# Slave4_flying_pcb_v1.net
KiCad netlist of a schematic drawn in Altium Designer
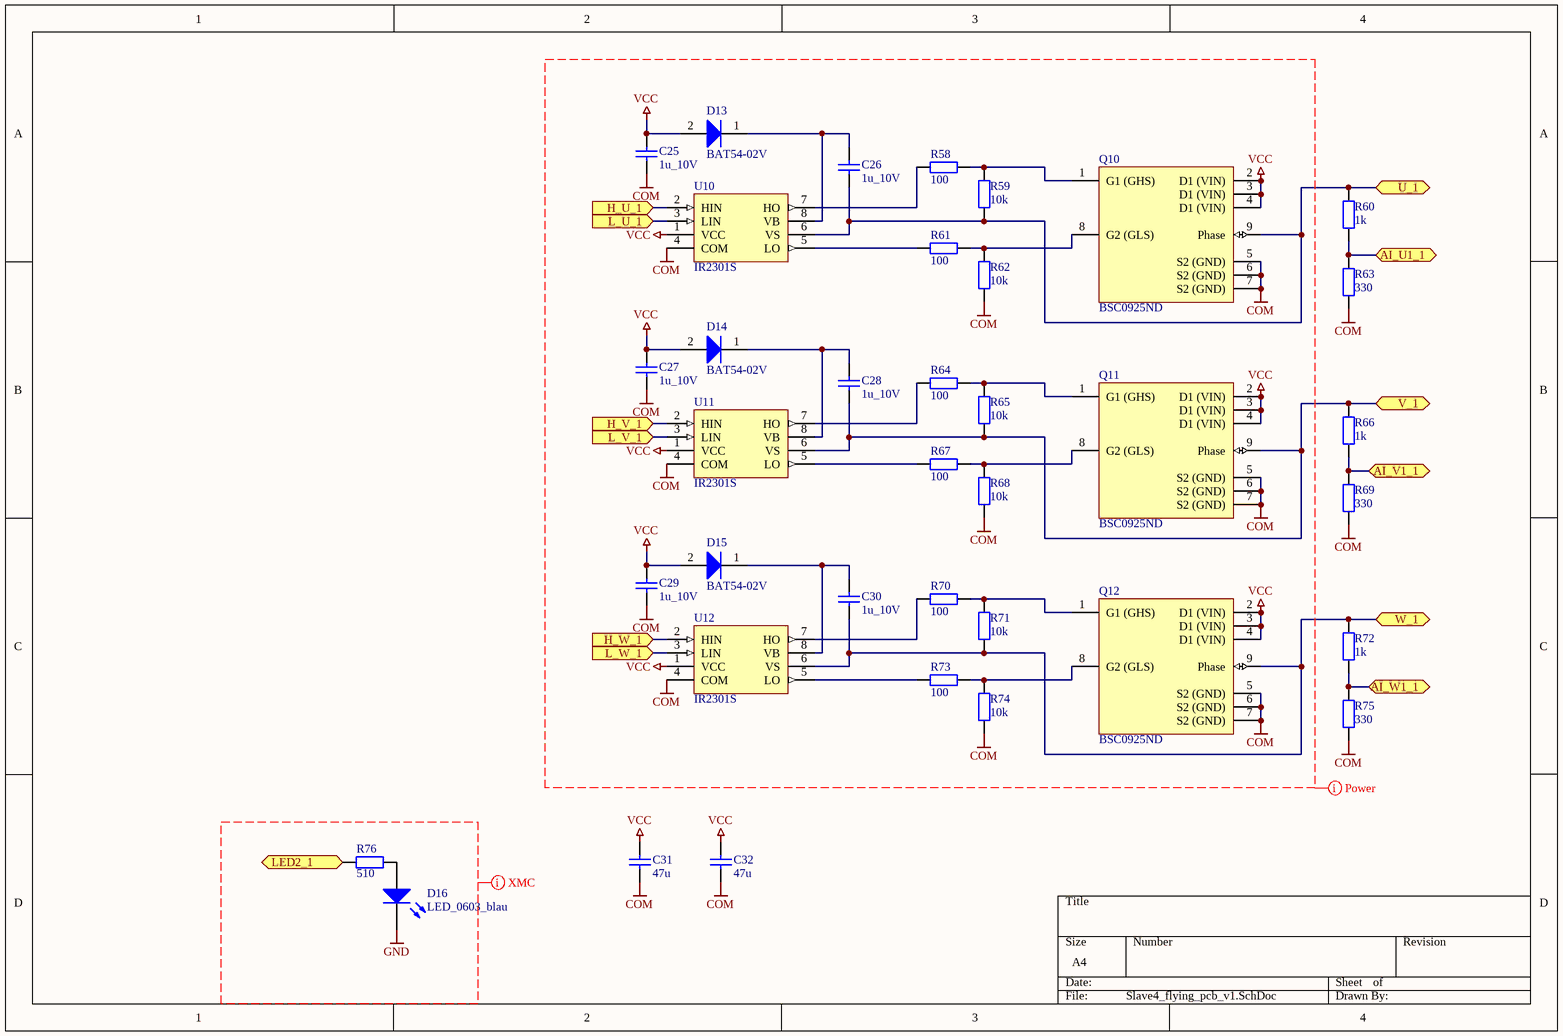
[diagram p0: Slave4_flying_pcb_v1.SchDoc]

(export (version "E")
  (design (tool "Eeschema 10.0.6"))
  (components
    (comp (ref "C25")
      (value "1u_10V")
      (footprint "1608[0603]")
      (fields (field (name "VOLTAGE") "10V"))
      (libsource (lib "Capacitors$") (part "Cap_133"))
    )
    (comp (ref "C26")
      (value "1u_10V")
      (footprint "1608[0603]")
      (fields (field (name "VOLTAGE") "10V"))
      (libsource (lib "Capacitors$") (part "Cap_133"))
    )
    (comp (ref "C27")
      (value "1u_10V")
      (footprint "1608[0603]")
      (fields (field (name "VOLTAGE") "10V"))
      (libsource (lib "Capacitors$") (part "Cap_133"))
    )
    (comp (ref "C28")
      (value "1u_10V")
      (footprint "1608[0603]")
      (fields (field (name "VOLTAGE") "10V"))
      (libsource (lib "Capacitors$") (part "Cap_133"))
    )
    (comp (ref "C29")
      (value "1u_10V")
      (footprint "1608[0603]")
      (fields (field (name "VOLTAGE") "10V"))
      (libsource (lib "Capacitors$") (part "Cap_133"))
    )
    (comp (ref "C30")
      (value "1u_10V")
      (footprint "1608[0603]")
      (fields (field (name "VOLTAGE") "10V"))
      (libsource (lib "Capacitors$") (part "Cap_133"))
    )
    (comp (ref "C31")
      (value "47u")
      (footprint "_0805")
      (fields (field (name "VOLTAGE") "50V"))
      (libsource (lib "Capacitors$") (part "Cap_133"))
    )
    (comp (ref "C32")
      (value "47u")
      (footprint "_0805")
      (fields (field (name "VOLTAGE") "50V"))
      (libsource (lib "Capacitors$") (part "Cap_133"))
    )
    (comp (ref "D13")
      (value "BAT54-02V")
      (footprint "INF-SC79_V")
      (description "Silicon Schottky Diode, SC79, Reel, Green")
      (fields (field (name "MANUFACTURER") "Infineon"))
      (libsource (lib "Pinus_V2") (part "BAT54-02V"))
    )
    (comp (ref "D14")
      (value "BAT54-02V")
      (footprint "INF-SC79_V")
      (description "Silicon Schottky Diode, SC79, Reel, Green")
      (fields (field (name "MANUFACTURER") "Infineon"))
      (libsource (lib "Pinus_V2") (part "BAT54-02V"))
    )
    (comp (ref "D15")
      (value "BAT54-02V")
      (footprint "INF-SC79_V")
      (description "Silicon Schottky Diode, SC79, Reel, Green")
      (fields (field (name "MANUFACTURER") "Infineon"))
      (libsource (lib "Pinus_V2") (part "BAT54-02V"))
    )
    (comp (ref "D16")
      (value "LED_0603_blau")
      (footprint "LED_0603")
      (libsource (lib "flying_pcb_v1") (part "DIODE_60"))
    )
    (comp (ref "Q10")
      (value "BSC0925ND")
      (footprint "INF-PG-TISON-8_V")
      (description "N-Channel OptiMOS Power-MOSFET, 30 V VDS, 40 A ID, -55 to 150 degC, PG-TISON-8, Reel, Green")
      (fields (field (name "MANUFACTURER") "Infineon"))
      (libsource (lib "Pinus_V2") (part "BSC0925ND"))
    )
    (comp (ref "Q11")
      (value "BSC0925ND")
      (footprint "INF-PG-TISON-8_V")
      (description "N-Channel OptiMOS Power-MOSFET, 30 V VDS, 40 A ID, -55 to 150 degC, PG-TISON-8, Reel, Green")
      (fields (field (name "MANUFACTURER") "Infineon"))
      (libsource (lib "Pinus_V2") (part "BSC0925ND"))
    )
    (comp (ref "Q12")
      (value "BSC0925ND")
      (footprint "INF-PG-TISON-8_V")
      (description "N-Channel OptiMOS Power-MOSFET, 30 V VDS, 40 A ID, -55 to 150 degC, PG-TISON-8, Reel, Green")
      (fields (field (name "MANUFACTURER") "Infineon"))
      (libsource (lib "Pinus_V2") (part "BSC0925ND"))
    )
    (comp (ref "R58")
      (value "100")
      (footprint "1608[0603]")
      (fields (field (name "Comment") "Res_0603"))
      (libsource (lib "") (part "Res_6_1"))
    )
    (comp (ref "R59")
      (value "10k")
      (footprint "1608[0603]")
      (fields (field (name "Comment") "Res_0603"))
      (libsource (lib "Resistors$") (part "Res_6"))
    )
    (comp (ref "R60")
      (value "1k")
      (footprint "1608[0603]")
      (fields (field (name "Comment") "Res_0603"))
      (libsource (lib "Resistors$") (part "Res_6"))
    )
    (comp (ref "R61")
      (value "100")
      (footprint "1608[0603]")
      (fields (field (name "Comment") "Res_0603"))
      (libsource (lib "") (part "Res_6_1"))
    )
    (comp (ref "R62")
      (value "10k")
      (footprint "1608[0603]")
      (fields (field (name "Comment") "Res_0603"))
      (libsource (lib "Resistors$") (part "Res_6"))
    )
    (comp (ref "R63")
      (value "330")
      (footprint "1608[0603]")
      (fields (field (name "Comment") "Res_0603"))
      (libsource (lib "Resistors$") (part "Res_6"))
    )
    (comp (ref "R64")
      (value "100")
      (footprint "1608[0603]")
      (fields (field (name "Comment") "Res_0603"))
      (libsource (lib "") (part "Res_6_1"))
    )
    (comp (ref "R65")
      (value "10k")
      (footprint "1608[0603]")
      (fields (field (name "Comment") "Res_0603"))
      (libsource (lib "Resistors$") (part "Res_6"))
    )
    (comp (ref "R66")
      (value "1k")
      (footprint "1608[0603]")
      (fields (field (name "Comment") "Res_0603"))
      (libsource (lib "Resistors$") (part "Res_6"))
    )
    (comp (ref "R67")
      (value "100")
      (footprint "1608[0603]")
      (fields (field (name "Comment") "Res_0603"))
      (libsource (lib "") (part "Res_6_1"))
    )
    (comp (ref "R68")
      (value "10k")
      (footprint "1608[0603]")
      (fields (field (name "Comment") "Res_0603"))
      (libsource (lib "Resistors$") (part "Res_6"))
    )
    (comp (ref "R69")
      (value "330")
      (footprint "1608[0603]")
      (fields (field (name "Comment") "Res_0603"))
      (libsource (lib "Resistors$") (part "Res_6"))
    )
    (comp (ref "R70")
      (value "100")
      (footprint "1608[0603]")
      (fields (field (name "Comment") "Res_0603"))
      (libsource (lib "") (part "Res_6_1"))
    )
    (comp (ref "R71")
      (value "10k")
      (footprint "1608[0603]")
      (fields (field (name "Comment") "Res_0603"))
      (libsource (lib "Resistors$") (part "Res_6"))
    )
    (comp (ref "R72")
      (value "1k")
      (footprint "1608[0603]")
      (fields (field (name "Comment") "Res_0603"))
      (libsource (lib "Resistors$") (part "Res_6"))
    )
    (comp (ref "R73")
      (value "100")
      (footprint "1608[0603]")
      (fields (field (name "Comment") "Res_0603"))
      (libsource (lib "") (part "Res_6_1"))
    )
    (comp (ref "R74")
      (value "10k")
      (footprint "1608[0603]")
      (fields (field (name "Comment") "Res_0603"))
      (libsource (lib "Resistors$") (part "Res_6"))
    )
    (comp (ref "R75")
      (value "330")
      (footprint "1608[0603]")
      (fields (field (name "Comment") "Res_0603"))
      (libsource (lib "Resistors$") (part "Res_6"))
    )
    (comp (ref "R76")
      (value "510")
      (footprint "1608[0603]")
      (fields (field (name "Comment") "Res_0603"))
      (libsource (lib "") (part "Res_6_2"))
    )
    (comp (ref "U10")
      (value "IR2301S")
      (footprint "SO-8_N")
      (description "High and Low Side Driver")
      (fields (field (name "PUBLISHER") "Altium Limited"))
      (libsource (lib "Pinus_V2") (part "IR2101S"))
    )
    (comp (ref "U11")
      (value "IR2301S")
      (footprint "SO-8_N")
      (description "High and Low Side Driver")
      (fields (field (name "PUBLISHER") "Altium Limited"))
      (libsource (lib "Pinus_V2") (part "IR2101S"))
    )
    (comp (ref "U12")
      (value "IR2301S")
      (footprint "SO-8_N")
      (description "High and Low Side Driver")
      (fields (field (name "PUBLISHER") "Altium Limited"))
      (libsource (lib "Pinus_V2") (part "IR2101S"))
    )
  )
  (nets
    (net (code "1") (name "/AI_U1_1") (class "Default")
      (node (ref "R60") (pin "2") (pinfunction "2_2") (pintype "passive"))
      (node (ref "R63") (pin "1") (pinfunction "1_1") (pintype "passive"))
    )
    (net (code "2") (name "/AI_V1_1") (class "Default")
      (node (ref "R66") (pin "2") (pinfunction "2_2") (pintype "passive"))
      (node (ref "R69") (pin "1") (pinfunction "1_1") (pintype "passive"))
    )
    (net (code "3") (name "/AI_W1_1") (class "Default")
      (node (ref "R72") (pin "2") (pinfunction "2_2") (pintype "passive"))
      (node (ref "R75") (pin "1") (pinfunction "1_1") (pintype "passive"))
    )
    (net (code "4") (name "/H_U_1") (class "Default")
      (node (ref "U10") (pin "2") (pinfunction "HIN_2") (pintype "input"))
    )
    (net (code "5") (name "/H_V_1") (class "Default")
      (node (ref "U11") (pin "2") (pinfunction "HIN_2") (pintype "input"))
    )
    (net (code "6") (name "/H_W_1") (class "Default")
      (node (ref "U12") (pin "2") (pinfunction "HIN_2") (pintype "input"))
    )
    (net (code "7") (name "/LED2_1") (class "Default")
      (node (ref "R76") (pin "1") (pinfunction "1_1") (pintype "passive"))
    )
    (net (code "8") (name "/L_U_1") (class "Default")
      (node (ref "U10") (pin "3") (pinfunction "LIN_3") (pintype "input"))
    )
    (net (code "9") (name "/L_V_1") (class "Default")
      (node (ref "U11") (pin "3") (pinfunction "LIN_3") (pintype "input"))
    )
    (net (code "10") (name "/L_W_1") (class "Default")
      (node (ref "U12") (pin "3") (pinfunction "LIN_3") (pintype "input"))
    )
    (net (code "11") (name "/U_1") (class "Default")
      (node (ref "C26") (pin "2") (pinfunction "2_2") (pintype "passive"))
      (node (ref "Q10") (pin "9") (pinfunction "Phase_9") (pintype "bidirectional"))
      (node (ref "R59") (pin "2") (pinfunction "2_2") (pintype "passive"))
      (node (ref "R60") (pin "1") (pinfunction "1_1") (pintype "passive"))
      (node (ref "U10") (pin "6") (pinfunction "VS_6") (pintype "power_in"))
    )
    (net (code "12") (name "/V_1") (class "Default")
      (node (ref "C28") (pin "2") (pinfunction "2_2") (pintype "passive"))
      (node (ref "Q11") (pin "9") (pinfunction "Phase_9") (pintype "bidirectional"))
      (node (ref "R65") (pin "2") (pinfunction "2_2") (pintype "passive"))
      (node (ref "R66") (pin "1") (pinfunction "1_1") (pintype "passive"))
      (node (ref "U11") (pin "6") (pinfunction "VS_6") (pintype "power_in"))
    )
    (net (code "13") (name "/W_1") (class "Default")
      (node (ref "C30") (pin "2") (pinfunction "2_2") (pintype "passive"))
      (node (ref "Q12") (pin "9") (pinfunction "Phase_9") (pintype "bidirectional"))
      (node (ref "R71") (pin "2") (pinfunction "2_2") (pintype "passive"))
      (node (ref "R72") (pin "1") (pinfunction "1_1") (pintype "passive"))
      (node (ref "U12") (pin "6") (pinfunction "VS_6") (pintype "power_in"))
    )
    (net (code "14") (name "COM") (class "Default")
      (node (ref "C25") (pin "2") (pinfunction "2_2") (pintype "passive"))
      (node (ref "C27") (pin "2") (pinfunction "2_2") (pintype "passive"))
      (node (ref "C29") (pin "2") (pinfunction "2_2") (pintype "passive"))
      (node (ref "C31") (pin "1") (pinfunction "1_1") (pintype "passive"))
      (node (ref "C32") (pin "1") (pinfunction "1_1") (pintype "passive"))
      (node (ref "Q10") (pin "5") (pinfunction "S2_(GND)_5") (pintype "passive"))
      (node (ref "Q10") (pin "6") (pinfunction "S2_(GND)_6") (pintype "passive"))
      (node (ref "Q10") (pin "7") (pinfunction "S2_(GND)_7") (pintype "passive"))
      (node (ref "Q11") (pin "5") (pinfunction "S2_(GND)_5") (pintype "passive"))
      (node (ref "Q11") (pin "6") (pinfunction "S2_(GND)_6") (pintype "passive"))
      (node (ref "Q11") (pin "7") (pinfunction "S2_(GND)_7") (pintype "passive"))
      (node (ref "Q12") (pin "5") (pinfunction "S2_(GND)_5") (pintype "passive"))
      (node (ref "Q12") (pin "6") (pinfunction "S2_(GND)_6") (pintype "passive"))
      (node (ref "Q12") (pin "7") (pinfunction "S2_(GND)_7") (pintype "passive"))
      (node (ref "R62") (pin "2") (pinfunction "2_2") (pintype "passive"))
      (node (ref "R63") (pin "2") (pinfunction "2_2") (pintype "passive"))
      (node (ref "R68") (pin "2") (pinfunction "2_2") (pintype "passive"))
      (node (ref "R69") (pin "2") (pinfunction "2_2") (pintype "passive"))
      (node (ref "R74") (pin "2") (pinfunction "2_2") (pintype "passive"))
      (node (ref "R75") (pin "2") (pinfunction "2_2") (pintype "passive"))
      (node (ref "U10") (pin "4") (pinfunction "COM_4") (pintype "power_in"))
      (node (ref "U11") (pin "4") (pinfunction "COM_4") (pintype "power_in"))
      (node (ref "U12") (pin "4") (pinfunction "COM_4") (pintype "power_in"))
    )
    (net (code "15") (name "GND") (class "Default")
      (node (ref "D16") (pin "2") (pinfunction "2_2") (pintype "passive"))
    )
    (net (code "16") (name "Net-(D13-K)") (class "Default")
      (node (ref "C26") (pin "1") (pinfunction "1_1") (pintype "passive"))
      (node (ref "D13") (pin "1") (pinfunction "K_1") (pintype "passive"))
      (node (ref "U10") (pin "8") (pinfunction "VB_8") (pintype "power_in"))
    )
    (net (code "17") (name "Net-(D14-K)") (class "Default")
      (node (ref "C28") (pin "1") (pinfunction "1_1") (pintype "passive"))
      (node (ref "D14") (pin "1") (pinfunction "K_1") (pintype "passive"))
      (node (ref "U11") (pin "8") (pinfunction "VB_8") (pintype "power_in"))
    )
    (net (code "18") (name "Net-(D15-K)") (class "Default")
      (node (ref "C30") (pin "1") (pinfunction "1_1") (pintype "passive"))
      (node (ref "D15") (pin "1") (pinfunction "K_1") (pintype "passive"))
      (node (ref "U12") (pin "8") (pinfunction "VB_8") (pintype "power_in"))
    )
    (net (code "19") (name "Net-(D16-Pad1)") (class "Default")
      (node (ref "D16") (pin "1") (pinfunction "1_1") (pintype "passive"))
      (node (ref "R76") (pin "2") (pinfunction "2_2") (pintype "passive"))
    )
    (net (code "20") (name "Net-(Q10-G1_(GHS))") (class "Default")
      (node (ref "Q10") (pin "1") (pinfunction "G1_(GHS)_1") (pintype "passive"))
      (node (ref "R58") (pin "1") (pinfunction "1_1") (pintype "passive"))
      (node (ref "R59") (pin "1") (pinfunction "1_1") (pintype "passive"))
    )
    (net (code "21") (name "Net-(Q10-G2_(GLS))") (class "Default")
      (node (ref "Q10") (pin "8") (pinfunction "G2_(GLS)_8") (pintype "passive"))
      (node (ref "R61") (pin "1") (pinfunction "1_1") (pintype "passive"))
      (node (ref "R62") (pin "1") (pinfunction "1_1") (pintype "passive"))
    )
    (net (code "22") (name "Net-(Q11-G1_(GHS))") (class "Default")
      (node (ref "Q11") (pin "1") (pinfunction "G1_(GHS)_1") (pintype "passive"))
      (node (ref "R64") (pin "1") (pinfunction "1_1") (pintype "passive"))
      (node (ref "R65") (pin "1") (pinfunction "1_1") (pintype "passive"))
    )
    (net (code "23") (name "Net-(Q11-G2_(GLS))") (class "Default")
      (node (ref "Q11") (pin "8") (pinfunction "G2_(GLS)_8") (pintype "passive"))
      (node (ref "R67") (pin "1") (pinfunction "1_1") (pintype "passive"))
      (node (ref "R68") (pin "1") (pinfunction "1_1") (pintype "passive"))
    )
    (net (code "24") (name "Net-(Q12-G1_(GHS))") (class "Default")
      (node (ref "Q12") (pin "1") (pinfunction "G1_(GHS)_1") (pintype "passive"))
      (node (ref "R70") (pin "1") (pinfunction "1_1") (pintype "passive"))
      (node (ref "R71") (pin "1") (pinfunction "1_1") (pintype "passive"))
    )
    (net (code "25") (name "Net-(Q12-G2_(GLS))") (class "Default")
      (node (ref "Q12") (pin "8") (pinfunction "G2_(GLS)_8") (pintype "passive"))
      (node (ref "R73") (pin "1") (pinfunction "1_1") (pintype "passive"))
      (node (ref "R74") (pin "1") (pinfunction "1_1") (pintype "passive"))
    )
    (net (code "26") (name "Net-(U10-HO)") (class "Default")
      (node (ref "R58") (pin "2") (pinfunction "2_2") (pintype "passive"))
      (node (ref "U10") (pin "7") (pinfunction "HO_7") (pintype "output"))
    )
    (net (code "27") (name "Net-(U10-LO)") (class "Default")
      (node (ref "R61") (pin "2") (pinfunction "2_2") (pintype "passive"))
      (node (ref "U10") (pin "5") (pinfunction "LO_5") (pintype "output"))
    )
    (net (code "28") (name "Net-(U11-HO)") (class "Default")
      (node (ref "R64") (pin "2") (pinfunction "2_2") (pintype "passive"))
      (node (ref "U11") (pin "7") (pinfunction "HO_7") (pintype "output"))
    )
    (net (code "29") (name "Net-(U11-LO)") (class "Default")
      (node (ref "R67") (pin "2") (pinfunction "2_2") (pintype "passive"))
      (node (ref "U11") (pin "5") (pinfunction "LO_5") (pintype "output"))
    )
    (net (code "30") (name "Net-(U12-HO)") (class "Default")
      (node (ref "R70") (pin "2") (pinfunction "2_2") (pintype "passive"))
      (node (ref "U12") (pin "7") (pinfunction "HO_7") (pintype "output"))
    )
    (net (code "31") (name "Net-(U12-LO)") (class "Default")
      (node (ref "R73") (pin "2") (pinfunction "2_2") (pintype "passive"))
      (node (ref "U12") (pin "5") (pinfunction "LO_5") (pintype "output"))
    )
    (net (code "32") (name "VCC") (class "Default")
      (node (ref "C25") (pin "1") (pinfunction "1_1") (pintype "passive"))
      (node (ref "C27") (pin "1") (pinfunction "1_1") (pintype "passive"))
      (node (ref "C29") (pin "1") (pinfunction "1_1") (pintype "passive"))
      (node (ref "C31") (pin "2") (pinfunction "2_2") (pintype "passive"))
      (node (ref "C32") (pin "2") (pinfunction "2_2") (pintype "passive"))
      (node (ref "D13") (pin "2") (pinfunction "A_2") (pintype "passive"))
      (node (ref "D14") (pin "2") (pinfunction "A_2") (pintype "passive"))
      (node (ref "D15") (pin "2") (pinfunction "A_2") (pintype "passive"))
      (node (ref "Q10") (pin "2") (pinfunction "D1_(VIN)_2") (pintype "passive"))
      (node (ref "Q10") (pin "3") (pinfunction "D1_(VIN)_3") (pintype "passive"))
      (node (ref "Q10") (pin "4") (pinfunction "D1_(VIN)_4") (pintype "passive"))
      (node (ref "Q11") (pin "2") (pinfunction "D1_(VIN)_2") (pintype "passive"))
      (node (ref "Q11") (pin "3") (pinfunction "D1_(VIN)_3") (pintype "passive"))
      (node (ref "Q11") (pin "4") (pinfunction "D1_(VIN)_4") (pintype "passive"))
      (node (ref "Q12") (pin "2") (pinfunction "D1_(VIN)_2") (pintype "passive"))
      (node (ref "Q12") (pin "3") (pinfunction "D1_(VIN)_3") (pintype "passive"))
      (node (ref "Q12") (pin "4") (pinfunction "D1_(VIN)_4") (pintype "passive"))
      (node (ref "U10") (pin "1") (pinfunction "VCC_1") (pintype "power_in"))
      (node (ref "U11") (pin "1") (pinfunction "VCC_1") (pintype "power_in"))
      (node (ref "U12") (pin "1") (pinfunction "VCC_1") (pintype "power_in"))
    )
  )
)
